# JQ6500-16P-V1_3.net
KiCad netlist of a schematic drawn in Altium Designer
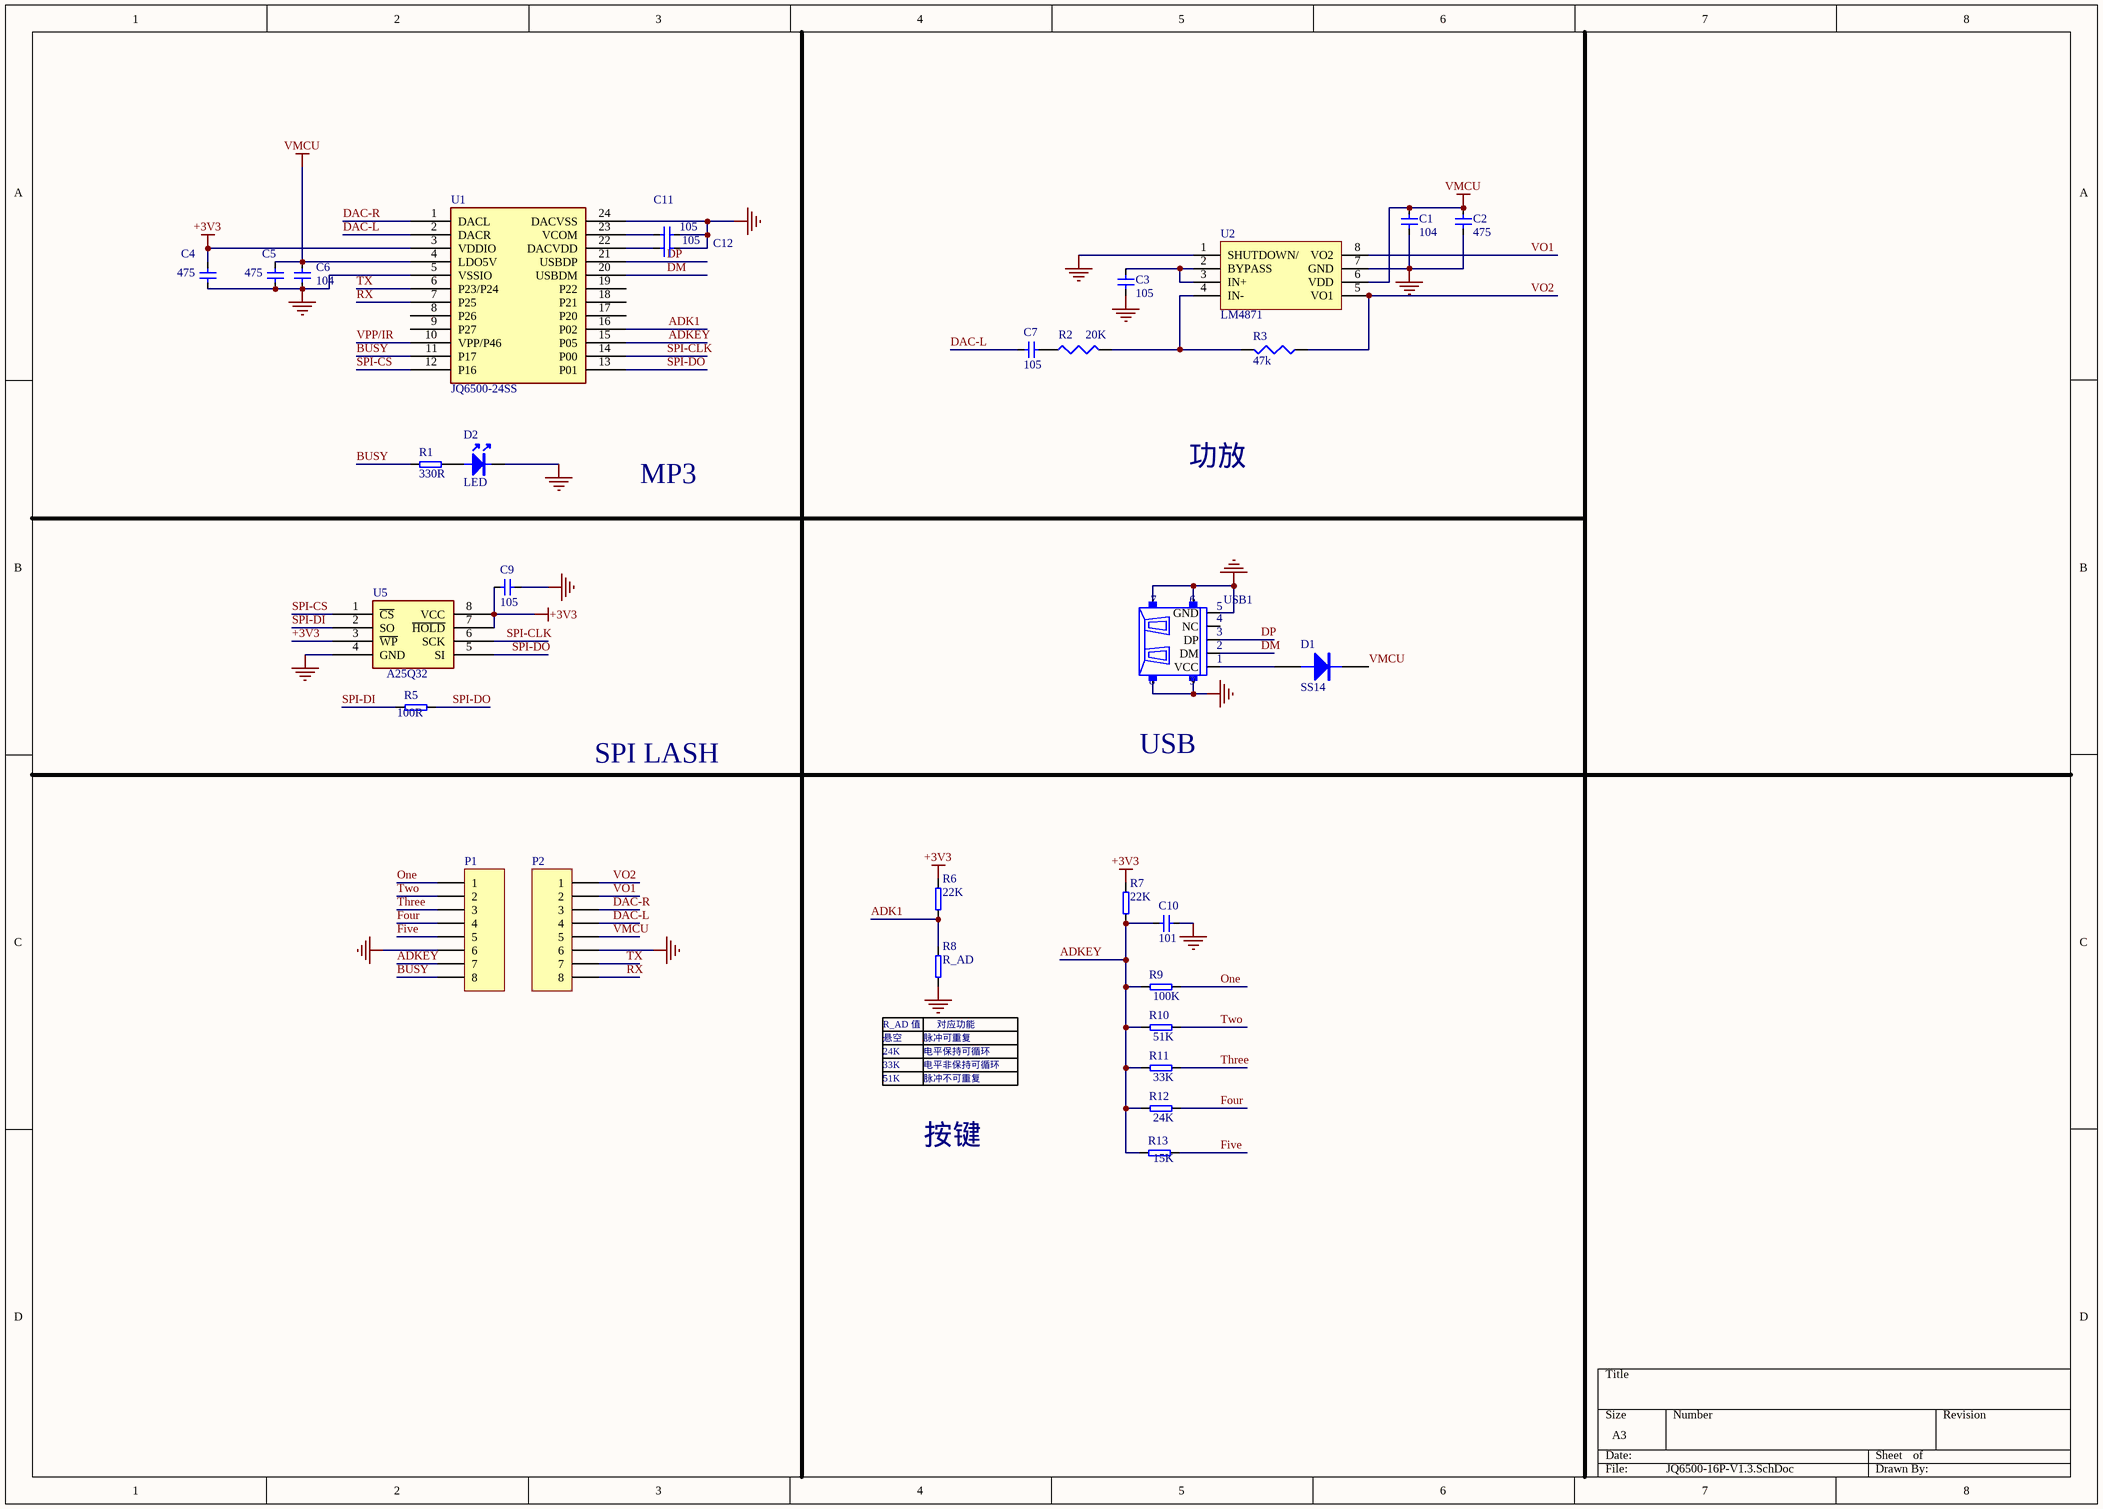
[diagram p0: JQ6500-16P-V1.3.SchDoc]

(export (version "E")
  (design (tool "Eeschema 10.0.6"))
  (components
    (comp (ref "C1")
      (value "104")
      (footprint "C0603")
      (description "Capacitor")
      (libsource (lib "*") (part "CAP"))
    )
    (comp (ref "C2")
      (value "475")
      (footprint "C0603")
      (description "Capacitor")
      (libsource (lib "*") (part "CAP"))
    )
    (comp (ref "C3")
      (value "105")
      (footprint "C0603")
      (description "Capacitor")
      (libsource (lib "*") (part "CAP"))
    )
    (comp (ref "C4")
      (value "475")
      (footprint "C0603")
      (description "Capacitor")
      (libsource (lib "*") (part "CAP"))
    )
    (comp (ref "C5")
      (value "475")
      (footprint "C0603")
      (description "Capacitor")
      (libsource (lib "*") (part "CAP"))
    )
    (comp (ref "C6")
      (value "104")
      (footprint "C0603")
      (description "Capacitor")
      (libsource (lib "*") (part "CAP"))
    )
    (comp (ref "C7")
      (value "105")
      (footprint "C0603")
      (description "Capacitor")
      (libsource (lib "*") (part "CAP"))
    )
    (comp (ref "C9")
      (value "105")
      (footprint "C0603")
      (description "Capacitor")
      (libsource (lib "*") (part "CAP"))
    )
    (comp (ref "C10")
      (value "101")
      (footprint "C0603")
      (description "Capacitor")
      (libsource (lib "*") (part "CAP"))
    )
    (comp (ref "C11")
      (value "105")
      (footprint "C0603")
      (description "Capacitor")
      (libsource (lib "*") (part "CAP"))
    )
    (comp (ref "C12")
      (value "105")
      (footprint "C0603")
      (description "Capacitor")
      (libsource (lib "*") (part "CAP"))
    )
    (comp (ref "D1")
      (value "SS14")
      (footprint "SOD123-1")
      (description "Diode")
      (libsource (lib "*") (part "DIODE"))
    )
    (comp (ref "D2") (value "LED") (footprint "0603") (libsource (lib "JQ6500PCB") (part "LED")))
    (comp (ref "P1")
      (value "Header 8")
      (footprint "HDR1X8")
      (description "Header, 8-Pin")
      (fields (field (name "PUBLISHER") "Altium Limited"))
      (libsource (lib "Miscellaneous Connectors") (part "Header 8"))
    )
    (comp (ref "P2")
      (value "Header 8")
      (footprint "HDR1X8")
      (description "Header, 8-Pin")
      (fields (field (name "PUBLISHER") "Altium Limited"))
      (libsource (lib "") (part "Header 8_1"))
    )
    (comp (ref "R1") (value "330R") (footprint "R0603") (libsource (lib "*") (part "RES")))
    (comp (ref "R2")
      (value "20K")
      (footprint "R0603")
      (description "0805.PcbLib")
      (fields (field (name "PUBLISHER") "Altium Limited"))
      (libsource (lib "*") (part "Res3"))
    )
    (comp (ref "R3")
      (value "47k")
      (footprint "R0603")
      (description "0805.PcbLib")
      (fields (field (name "PUBLISHER") "Altium Limited"))
      (libsource (lib "*") (part "Res3"))
    )
    (comp (ref "R5") (value "100R") (footprint "R0603") (libsource (lib "*") (part "RES")))
    (comp (ref "R6") (value "22K") (footprint "R0603") (libsource (lib "*") (part "RES")))
    (comp (ref "R7") (value "22K") (footprint "R0603") (libsource (lib "*") (part "RES")))
    (comp (ref "R8") (value "R_AD") (footprint "R0603") (libsource (lib "*") (part "RES")))
    (comp (ref "R9") (value "100K") (footprint "R0603") (libsource (lib "*") (part "RES")))
    (comp (ref "R10") (value "51K") (footprint "R0603") (libsource (lib "*") (part "RES")))
    (comp (ref "R11") (value "33K") (footprint "R0603") (libsource (lib "*") (part "RES")))
    (comp (ref "R12") (value "24K") (footprint "R0603") (libsource (lib "*") (part "RES")))
    (comp (ref "R13") (value "15K") (footprint "R0603") (libsource (lib "*") (part "RES")))
    (comp (ref "U1") (value "JQ6500-24SS") (footprint "SSOP24") (libsource (lib "*") (part "AC1094")))
    (comp (ref "U2") (value "LM4871") (footprint "SOP_8") (libsource (lib "IC") (part "LM4890")))
    (comp (ref "U5") (value "A25Q32") (footprint "W25X16") (libsource (lib "*") (part "A25Q32")))
    (comp (ref "USB1") (value "USB-5PIN") (footprint "USB-5PIN") (libsource (lib "*") (part "USB-5PIN")))
  )
  (nets
    (net (code "1") (name "+3V3") (class "Default")
      (node (ref "C4") (pin "1") (pinfunction "1_1") (pintype "passive"))
      (node (ref "C9") (pin "1") (pinfunction "1_1") (pintype "passive"))
      (node (ref "R6") (pin "2") (pinfunction "2_2") (pintype "passive"))
      (node (ref "R7") (pin "2") (pinfunction "2_2") (pintype "passive"))
      (node (ref "U1") (pin "3") (pinfunction "VDDIO_3") (pintype "passive"))
      (node (ref "U5") (pin "3") (pinfunction "~{WP}_3") (pintype "passive"))
      (node (ref "U5") (pin "7") (pinfunction "~{HOLD}_7") (pintype "passive"))
      (node (ref "U5") (pin "8") (pinfunction "VCC_8") (pintype "passive"))
    )
    (net (code "2") (name "/ADK1") (class "Default")
      (node (ref "R6") (pin "1") (pinfunction "1_1") (pintype "passive"))
      (node (ref "R8") (pin "2") (pinfunction "2_2") (pintype "passive"))
      (node (ref "U1") (pin "16") (pinfunction "P02_16") (pintype "passive"))
    )
    (net (code "3") (name "/ADKEY") (class "Default")
      (node (ref "C10") (pin "2") (pinfunction "2_2") (pintype "passive"))
      (node (ref "P1") (pin "7") (pinfunction "7_7") (pintype "passive"))
      (node (ref "R10") (pin "2") (pinfunction "2_2") (pintype "passive"))
      (node (ref "R11") (pin "2") (pinfunction "2_2") (pintype "passive"))
      (node (ref "R12") (pin "2") (pinfunction "2_2") (pintype "passive"))
      (node (ref "R13") (pin "2") (pinfunction "2_2") (pintype "passive"))
      (node (ref "R7") (pin "1") (pinfunction "1_1") (pintype "passive"))
      (node (ref "R9") (pin "2") (pinfunction "2_2") (pintype "passive"))
      (node (ref "U1") (pin "15") (pinfunction "P05_15") (pintype "passive"))
    )
    (net (code "4") (name "/BUSY") (class "Default")
      (node (ref "P1") (pin "8") (pinfunction "8_8") (pintype "passive"))
      (node (ref "R1") (pin "2") (pinfunction "2_2") (pintype "passive"))
      (node (ref "U1") (pin "11") (pinfunction "P17_11") (pintype "passive"))
    )
    (net (code "5") (name "/DAC-L") (class "Default")
      (node (ref "C7") (pin "1") (pinfunction "1_1") (pintype "passive"))
      (node (ref "P2") (pin "4") (pinfunction "4_4") (pintype "passive"))
      (node (ref "U1") (pin "2") (pinfunction "DACR_2") (pintype "passive"))
    )
    (net (code "6") (name "/DAC-R") (class "Default")
      (node (ref "P2") (pin "3") (pinfunction "3_3") (pintype "passive"))
      (node (ref "U1") (pin "1") (pinfunction "DACL_1") (pintype "passive"))
    )
    (net (code "7") (name "/DM") (class "Default")
      (node (ref "U1") (pin "20") (pinfunction "USBDM_20") (pintype "passive"))
      (node (ref "USB1") (pin "2") (pinfunction "DM_2") (pintype "passive"))
    )
    (net (code "8") (name "/DP") (class "Default")
      (node (ref "U1") (pin "21") (pinfunction "USBDP_21") (pintype "passive"))
      (node (ref "USB1") (pin "3") (pinfunction "DP_3") (pintype "passive"))
    )
    (net (code "9") (name "/Five") (class "Default")
      (node (ref "P1") (pin "5") (pinfunction "5_5") (pintype "passive"))
      (node (ref "R13") (pin "1") (pinfunction "1_1") (pintype "passive"))
    )
    (net (code "10") (name "/Four") (class "Default")
      (node (ref "P1") (pin "4") (pinfunction "4_4") (pintype "passive"))
      (node (ref "R12") (pin "1") (pinfunction "1_1") (pintype "passive"))
    )
    (net (code "11") (name "/One") (class "Default")
      (node (ref "P1") (pin "1") (pinfunction "1_1") (pintype "passive"))
      (node (ref "R9") (pin "1") (pinfunction "1_1") (pintype "passive"))
    )
    (net (code "12") (name "/RX") (class "Default")
      (node (ref "P2") (pin "8") (pinfunction "8_8") (pintype "passive"))
      (node (ref "U1") (pin "7") (pinfunction "P25_7") (pintype "passive"))
    )
    (net (code "13") (name "/SPI-CLK") (class "Default")
      (node (ref "U1") (pin "14") (pinfunction "P00_14") (pintype "passive"))
      (node (ref "U5") (pin "6") (pinfunction "SCK_6") (pintype "passive"))
    )
    (net (code "14") (name "/SPI-CS") (class "Default")
      (node (ref "U1") (pin "12") (pinfunction "P16_12") (pintype "passive"))
      (node (ref "U5") (pin "1") (pinfunction "~{CS}_1") (pintype "passive"))
    )
    (net (code "15") (name "/SPI-DI") (class "Default")
      (node (ref "R5") (pin "2") (pinfunction "2_2") (pintype "passive"))
      (node (ref "U5") (pin "2") (pinfunction "SO_2") (pintype "passive"))
    )
    (net (code "16") (name "/SPI-DO") (class "Default")
      (node (ref "R5") (pin "1") (pinfunction "1_1") (pintype "passive"))
      (node (ref "U1") (pin "13") (pinfunction "P01_13") (pintype "passive"))
      (node (ref "U5") (pin "5") (pinfunction "SI_5") (pintype "passive"))
    )
    (net (code "17") (name "/TX") (class "Default")
      (node (ref "P2") (pin "7") (pinfunction "7_7") (pintype "passive"))
      (node (ref "U1") (pin "6") (pinfunction "P23/P24_6") (pintype "passive"))
    )
    (net (code "18") (name "/Three") (class "Default")
      (node (ref "P1") (pin "3") (pinfunction "3_3") (pintype "passive"))
      (node (ref "R11") (pin "1") (pinfunction "1_1") (pintype "passive"))
    )
    (net (code "19") (name "/Two") (class "Default")
      (node (ref "P1") (pin "2") (pinfunction "2_2") (pintype "passive"))
      (node (ref "R10") (pin "1") (pinfunction "1_1") (pintype "passive"))
    )
    (net (code "20") (name "/VO1") (class "Default")
      (node (ref "P2") (pin "2") (pinfunction "2_2") (pintype "passive"))
      (node (ref "U2") (pin "8") (pinfunction "VO2_8") (pintype "passive"))
    )
    (net (code "21") (name "/VO2") (class "Default")
      (node (ref "P2") (pin "1") (pinfunction "1_1") (pintype "passive"))
      (node (ref "R3") (pin "1") (pinfunction "1_1") (pintype "passive"))
      (node (ref "U2") (pin "5") (pinfunction "VO1_5") (pintype "passive"))
    )
    (net (code "22") (name "/VPP{slash}IR") (class "Default")
      (node (ref "U1") (pin "10") (pinfunction "VPP/P46_10") (pintype "passive"))
    )
    (net (code "23") (name "GND") (class "Default")
      (node (ref "C1") (pin "1") (pinfunction "1_1") (pintype "passive"))
      (node (ref "C10") (pin "1") (pinfunction "1_1") (pintype "passive"))
      (node (ref "C11") (pin "2") (pinfunction "2_2") (pintype "passive"))
      (node (ref "C12") (pin "1") (pinfunction "1_1") (pintype "passive"))
      (node (ref "C2") (pin "1") (pinfunction "1_1") (pintype "passive"))
      (node (ref "C3") (pin "1") (pinfunction "1_1") (pintype "passive"))
      (node (ref "C4") (pin "2") (pinfunction "2_2") (pintype "passive"))
      (node (ref "C5") (pin "2") (pinfunction "2_2") (pintype "passive"))
      (node (ref "C6") (pin "2") (pinfunction "2_2") (pintype "passive"))
      (node (ref "C9") (pin "2") (pinfunction "2_2") (pintype "passive"))
      (node (ref "D2") (pin "2") (pinfunction "2_2") (pintype "passive"))
      (node (ref "P1") (pin "6") (pinfunction "6_6") (pintype "passive"))
      (node (ref "P2") (pin "6") (pinfunction "6_6") (pintype "passive"))
      (node (ref "R8") (pin "1") (pinfunction "1_1") (pintype "passive"))
      (node (ref "U1") (pin "24") (pinfunction "DACVSS_24") (pintype "passive"))
      (node (ref "U1") (pin "5") (pinfunction "VSSIO_5") (pintype "passive"))
      (node (ref "U2") (pin "1") (pinfunction "SHUTDOWN/_1") (pintype "passive"))
      (node (ref "U2") (pin "7") (pinfunction "GND_7") (pintype "passive"))
      (node (ref "U5") (pin "4") (pinfunction "GND_4") (pintype "passive"))
      (node (ref "USB1") (pin "5") (pinfunction "GND_5") (pintype "passive"))
      (node (ref "USB1") (pin "6") (pinfunction "6_6") (pintype "passive"))
      (node (ref "USB1") (pin "7") (pinfunction "7_7") (pintype "passive"))
      (node (ref "USB1") (pin "8") (pinfunction "8_8") (pintype "passive"))
      (node (ref "USB1") (pin "9") (pinfunction "9_9") (pintype "passive"))
    )
    (net (code "24") (name "Net-(C7-Pad2)") (class "Default")
      (node (ref "C7") (pin "2") (pinfunction "2_2") (pintype "passive"))
      (node (ref "R2") (pin "1") (pinfunction "1_1") (pintype "passive"))
    )
    (net (code "25") (name "Net-(D1-A)") (class "Default")
      (node (ref "D1") (pin "1") (pinfunction "A_1") (pintype "passive"))
      (node (ref "USB1") (pin "1") (pinfunction "VCC_1") (pintype "passive"))
    )
    (net (code "26") (name "Net-(D2-Pad1)") (class "Default")
      (node (ref "D2") (pin "1") (pinfunction "1_1") (pintype "passive"))
      (node (ref "R1") (pin "1") (pinfunction "1_1") (pintype "passive"))
    )
    (net (code "27") (name "Net-(U1-DACVDD)") (class "Default")
      (node (ref "C12") (pin "2") (pinfunction "2_2") (pintype "passive"))
      (node (ref "U1") (pin "22") (pinfunction "DACVDD_22") (pintype "passive"))
    )
    (net (code "28") (name "Net-(U1-VCOM)") (class "Default")
      (node (ref "C11") (pin "1") (pinfunction "1_1") (pintype "passive"))
      (node (ref "U1") (pin "23") (pinfunction "VCOM_23") (pintype "passive"))
    )
    (net (code "29") (name "Net-(U2-BYPASS)") (class "Default")
      (node (ref "C3") (pin "2") (pinfunction "2_2") (pintype "passive"))
      (node (ref "U2") (pin "2") (pinfunction "BYPASS_2") (pintype "passive"))
      (node (ref "U2") (pin "3") (pinfunction "IN+_3") (pintype "passive"))
    )
    (net (code "30") (name "Net-(U2-IN-)") (class "Default")
      (node (ref "R2") (pin "2") (pinfunction "2_2") (pintype "passive"))
      (node (ref "R3") (pin "2") (pinfunction "2_2") (pintype "passive"))
      (node (ref "U2") (pin "4") (pinfunction "IN-_4") (pintype "passive"))
    )
    (net (code "31") (name "VMCU") (class "Default")
      (node (ref "C1") (pin "2") (pinfunction "2_2") (pintype "passive"))
      (node (ref "C2") (pin "2") (pinfunction "2_2") (pintype "passive"))
      (node (ref "C5") (pin "1") (pinfunction "1_1") (pintype "passive"))
      (node (ref "C6") (pin "1") (pinfunction "1_1") (pintype "passive"))
      (node (ref "D1") (pin "2") (pinfunction "K_2") (pintype "passive"))
      (node (ref "P2") (pin "5") (pinfunction "5_5") (pintype "passive"))
      (node (ref "U1") (pin "4") (pinfunction "LDO5V_4") (pintype "passive"))
      (node (ref "U2") (pin "6") (pinfunction "VDD_6") (pintype "passive"))
    )
    (net (code "32") (name "unconnected-(U1-P20-Pad17)") (class "Default")
      (node (ref "U1") (pin "17") (pinfunction "P20_17") (pintype "passive"))
    )
    (net (code "33") (name "unconnected-(U1-P21-Pad18)") (class "Default")
      (node (ref "U1") (pin "18") (pinfunction "P21_18") (pintype "passive"))
    )
    (net (code "34") (name "unconnected-(U1-P22-Pad19)") (class "Default")
      (node (ref "U1") (pin "19") (pinfunction "P22_19") (pintype "passive"))
    )
    (net (code "35") (name "unconnected-(U1-P26-Pad8)") (class "Default")
      (node (ref "U1") (pin "8") (pinfunction "P26_8") (pintype "passive"))
    )
    (net (code "36") (name "unconnected-(U1-P27-Pad9)") (class "Default")
      (node (ref "U1") (pin "9") (pinfunction "P27_9") (pintype "passive"))
    )
    (net (code "37") (name "unconnected-(USB1-NC-Pad4)") (class "Default")
      (node (ref "USB1") (pin "4") (pinfunction "NC_4") (pintype "passive"))
    )
  )
)
